# Slave_Mux.net
KiCad netlist of a schematic drawn in EAGLE
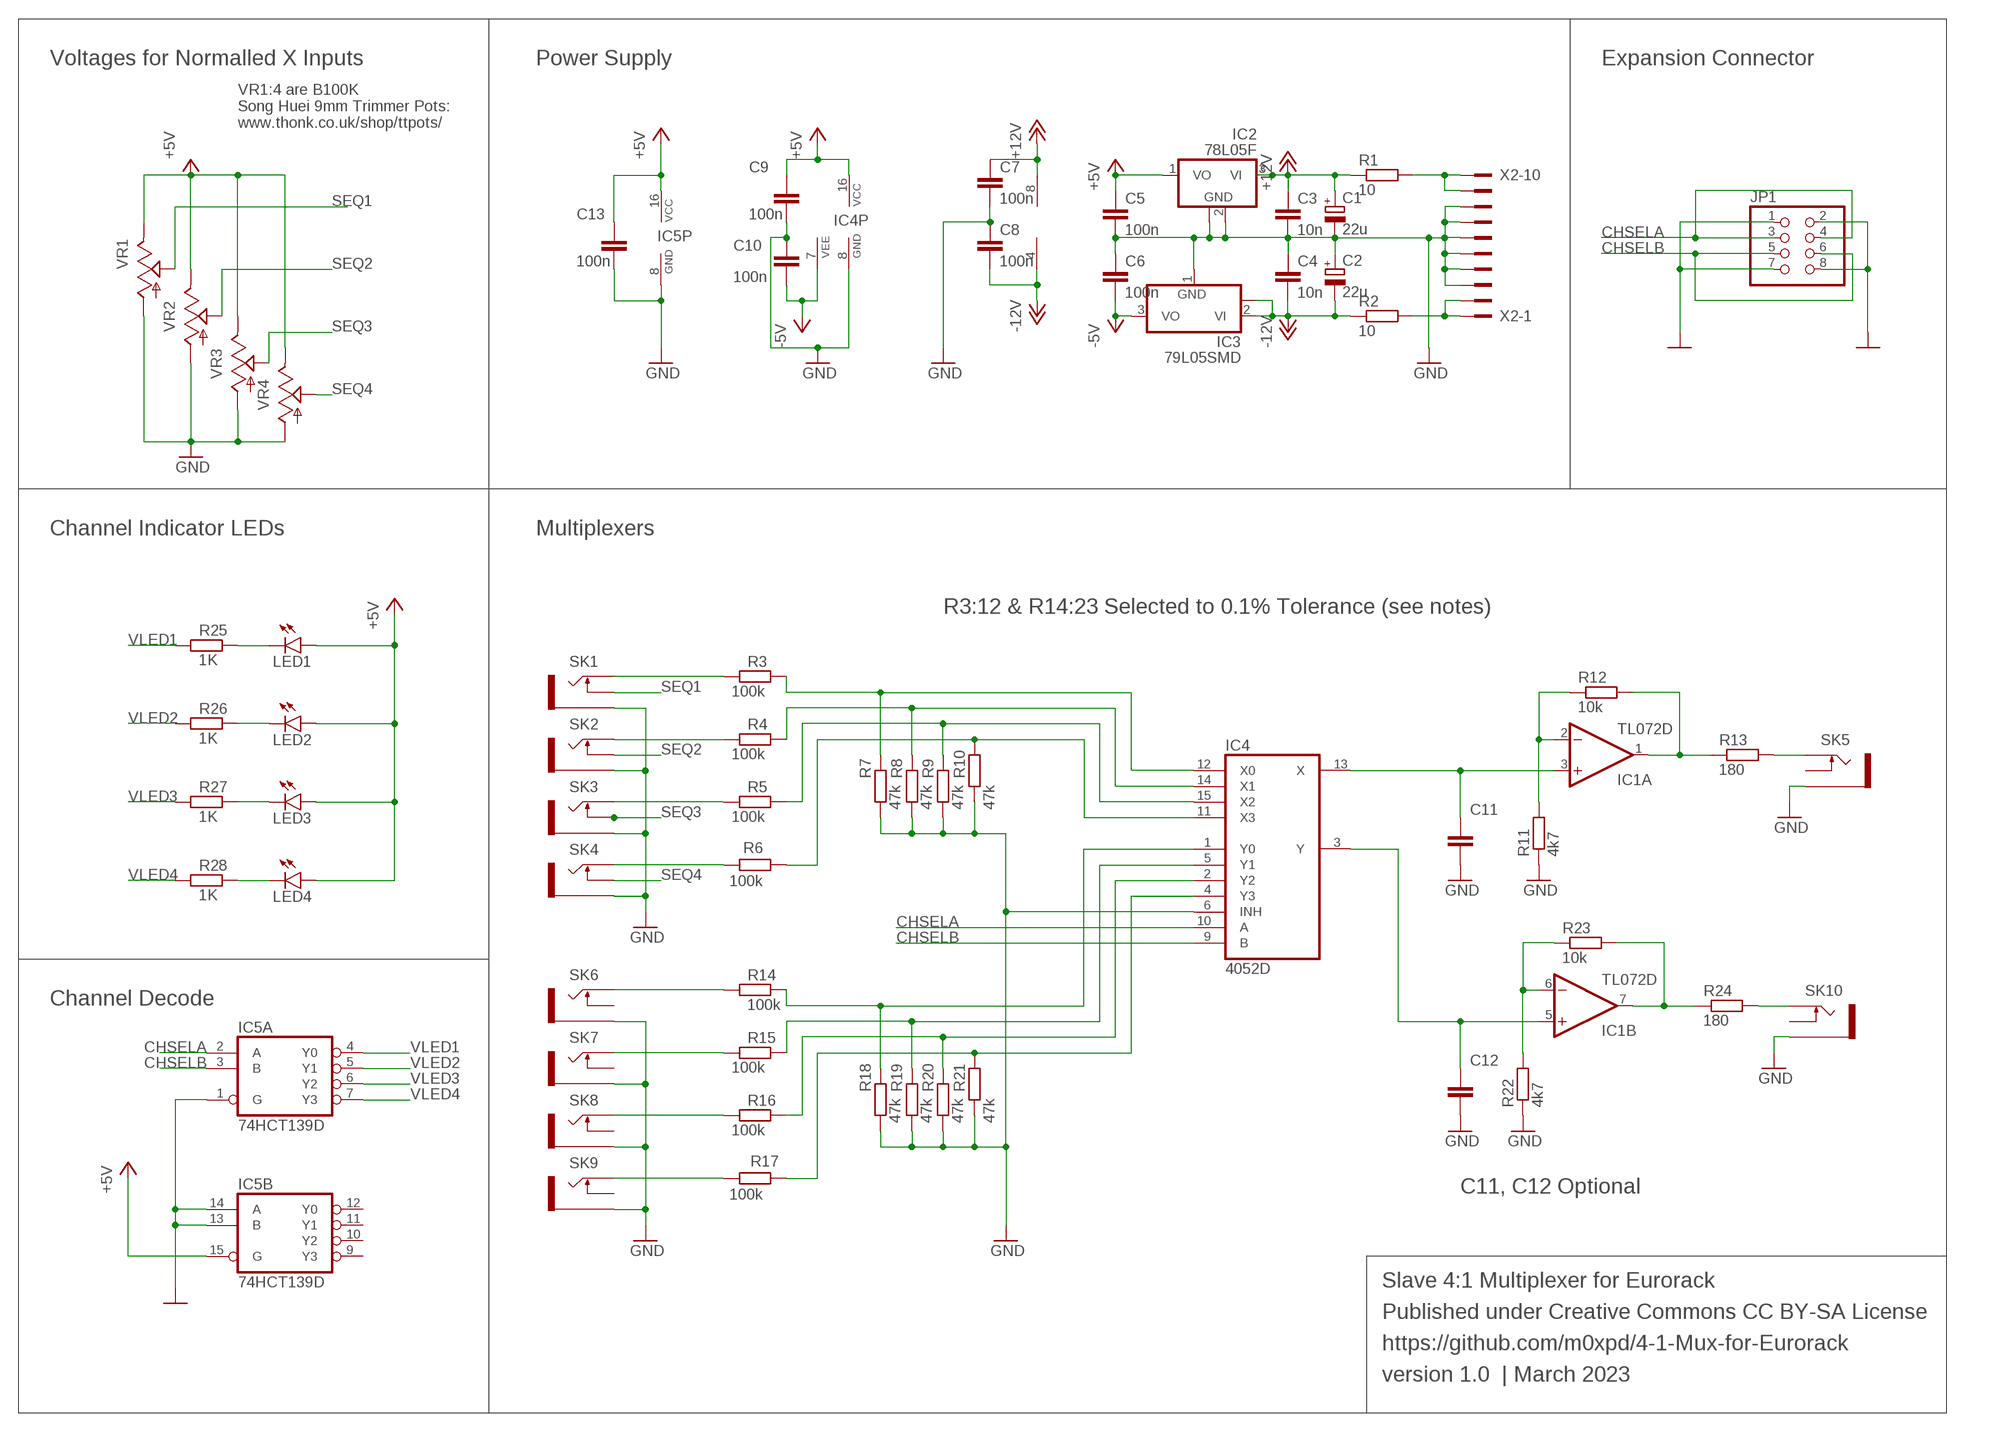
[diagram p0: schematic, sheet 1]

(export (version "E")
  (design (tool "Eeschema 10.0.6"))
  (components
    (comp (ref "C1")
      (value "22u")
      (footprint "eagle-import:153CLV-0505")
      (libsource (lib "eagle-import") (part "CPOL-EU153CLV-0505"))
    )
    (comp (ref "C2")
      (value "22u")
      (footprint "eagle-import:153CLV-0505")
      (libsource (lib "eagle-import") (part "CPOL-EU153CLV-0505"))
    )
    (comp (ref "C3")
      (value "10n")
      (footprint "eagle-import:C1206")
      (libsource (lib "eagle-import") (part "C-EUC1206"))
    )
    (comp (ref "C4")
      (value "10n")
      (footprint "eagle-import:C1206")
      (libsource (lib "eagle-import") (part "C-EUC1206"))
    )
    (comp (ref "C5")
      (value "100n")
      (footprint "eagle-import:C1206")
      (libsource (lib "eagle-import") (part "C-EUC1206"))
    )
    (comp (ref "C6")
      (value "100n")
      (footprint "eagle-import:C1206")
      (libsource (lib "eagle-import") (part "C-EUC1206"))
    )
    (comp (ref "C7")
      (value "100n")
      (footprint "eagle-import:C1206")
      (libsource (lib "eagle-import") (part "C-EUC1206"))
    )
    (comp (ref "C8")
      (value "100n")
      (footprint "eagle-import:C1206")
      (libsource (lib "eagle-import") (part "C-EUC1206"))
    )
    (comp (ref "C9")
      (value "100n")
      (footprint "eagle-import:C1206")
      (libsource (lib "eagle-import") (part "C-EUC1206"))
    )
    (comp (ref "C10")
      (value "100n")
      (footprint "eagle-import:C1206")
      (libsource (lib "eagle-import") (part "C-EUC1206"))
    )
    (comp (ref "C11")
      (value "C-EUC1206")
      (footprint "eagle-import:C1206")
      (libsource (lib "eagle-import") (part "C-EUC1206"))
    )
    (comp (ref "C12")
      (value "C-EUC1206")
      (footprint "eagle-import:C1206")
      (libsource (lib "eagle-import") (part "C-EUC1206"))
    )
    (comp (ref "C13")
      (value "100n")
      (footprint "eagle-import:C1206")
      (libsource (lib "eagle-import") (part "C-EUC1206"))
    )
    (comp (ref "IC1")
      (value "TL072D")
      (footprint "eagle-import:SO08")
      (libsource (lib "eagle-import") (part "TL072D"))
    )
    (comp (ref "IC2")
      (value "78L05F")
      (footprint "eagle-import:SOT89")
      (libsource (lib "eagle-import") (part "78LF05"))
    )
    (comp (ref "IC3")
      (value "79L05SMD")
      (footprint "eagle-import:SOT89")
      (libsource (lib "eagle-import") (part "79L05SMD"))
    )
    (comp (ref "IC4")
      (value "4052D")
      (footprint "eagle-import:SO16")
      (libsource (lib "eagle-import") (part "4052D"))
    )
    (comp (ref "IC5")
      (value "74HCT139D")
      (footprint "eagle-import:SO16")
      (libsource (lib "eagle-import") (part "74139DHCT"))
    )
    (comp (ref "JP1")
      (value "PINHD-2X4")
      (footprint "eagle-import:2X04")
      (libsource (lib "eagle-import") (part "PINHD-2X4"))
    )
    (comp (ref "LED1")
      (value "LED3MM")
      (footprint "eagle-import:LED3MM")
      (libsource (lib "eagle-import") (part "LED3MM"))
    )
    (comp (ref "LED2")
      (value "LED3MM")
      (footprint "eagle-import:LED3MM")
      (libsource (lib "eagle-import") (part "LED3MM"))
    )
    (comp (ref "LED3")
      (value "LED3MM")
      (footprint "eagle-import:LED3MM")
      (libsource (lib "eagle-import") (part "LED3MM"))
    )
    (comp (ref "LED4")
      (value "LED3MM")
      (footprint "eagle-import:LED3MM")
      (libsource (lib "eagle-import") (part "LED3MM"))
    )
    (comp (ref "R1")
      (value "10")
      (footprint "eagle-import:M1206")
      (libsource (lib "eagle-import") (part "R-EU_M1206"))
    )
    (comp (ref "R2")
      (value "10")
      (footprint "eagle-import:M1206")
      (libsource (lib "eagle-import") (part "R-EU_M1206"))
    )
    (comp (ref "R3")
      (value "100k")
      (footprint "eagle-import:M1206")
      (libsource (lib "eagle-import") (part "R-EU_M1206"))
    )
    (comp (ref "R4")
      (value "100k")
      (footprint "eagle-import:M1206")
      (libsource (lib "eagle-import") (part "R-EU_M1206"))
    )
    (comp (ref "R5")
      (value "100k")
      (footprint "eagle-import:M1206")
      (libsource (lib "eagle-import") (part "R-EU_M1206"))
    )
    (comp (ref "R6")
      (value "100k")
      (footprint "eagle-import:M1206")
      (libsource (lib "eagle-import") (part "R-EU_M1206"))
    )
    (comp (ref "R7")
      (value "47k")
      (footprint "eagle-import:M1206")
      (libsource (lib "eagle-import") (part "R-EU_M1206"))
    )
    (comp (ref "R8")
      (value "47k")
      (footprint "eagle-import:M1206")
      (libsource (lib "eagle-import") (part "R-EU_M1206"))
    )
    (comp (ref "R9")
      (value "47k")
      (footprint "eagle-import:M1206")
      (libsource (lib "eagle-import") (part "R-EU_M1206"))
    )
    (comp (ref "R10")
      (value "47k")
      (footprint "eagle-import:M1206")
      (libsource (lib "eagle-import") (part "R-EU_M1206"))
    )
    (comp (ref "R11")
      (value "4k7")
      (footprint "eagle-import:R1206")
      (libsource (lib "eagle-import") (part "R-EU_R1206"))
    )
    (comp (ref "R12")
      (value "10k")
      (footprint "eagle-import:R1206")
      (libsource (lib "eagle-import") (part "R-EU_R1206"))
    )
    (comp (ref "R13")
      (value "180")
      (footprint "eagle-import:M1206")
      (libsource (lib "eagle-import") (part "R-EU_M1206"))
    )
    (comp (ref "R14")
      (value "100k")
      (footprint "eagle-import:M1206")
      (libsource (lib "eagle-import") (part "R-EU_M1206"))
    )
    (comp (ref "R15")
      (value "100k")
      (footprint "eagle-import:M1206")
      (libsource (lib "eagle-import") (part "R-EU_M1206"))
    )
    (comp (ref "R16")
      (value "100k")
      (footprint "eagle-import:M1206")
      (libsource (lib "eagle-import") (part "R-EU_M1206"))
    )
    (comp (ref "R17")
      (value "100k")
      (footprint "eagle-import:M1206")
      (libsource (lib "eagle-import") (part "R-EU_M1206"))
    )
    (comp (ref "R18")
      (value "47k")
      (footprint "eagle-import:M1206")
      (libsource (lib "eagle-import") (part "R-EU_M1206"))
    )
    (comp (ref "R19")
      (value "47k")
      (footprint "eagle-import:M1206")
      (libsource (lib "eagle-import") (part "R-EU_M1206"))
    )
    (comp (ref "R20")
      (value "47k")
      (footprint "eagle-import:M1206")
      (libsource (lib "eagle-import") (part "R-EU_M1206"))
    )
    (comp (ref "R21")
      (value "47k")
      (footprint "eagle-import:M1206")
      (libsource (lib "eagle-import") (part "R-EU_M1206"))
    )
    (comp (ref "R22")
      (value "4k7")
      (footprint "eagle-import:R1206")
      (libsource (lib "eagle-import") (part "R-EU_R1206"))
    )
    (comp (ref "R23")
      (value "10k")
      (footprint "eagle-import:R1206")
      (libsource (lib "eagle-import") (part "R-EU_R1206"))
    )
    (comp (ref "R24")
      (value "180")
      (footprint "eagle-import:M1206")
      (libsource (lib "eagle-import") (part "R-EU_M1206"))
    )
    (comp (ref "R25")
      (value "1K")
      (footprint "eagle-import:M1206")
      (libsource (lib "eagle-import") (part "R-EU_M1206"))
    )
    (comp (ref "R26")
      (value "1K")
      (footprint "eagle-import:M1206")
      (libsource (lib "eagle-import") (part "R-EU_M1206"))
    )
    (comp (ref "R27")
      (value "1K")
      (footprint "eagle-import:M1206")
      (libsource (lib "eagle-import") (part "R-EU_M1206"))
    )
    (comp (ref "R28")
      (value "1K")
      (footprint "eagle-import:M1206")
      (libsource (lib "eagle-import") (part "R-EU_M1206"))
    )
    (comp (ref "SK1")
      (value "THONKICONN_JACK")
      (footprint "eagle-import:WQP-PJ301M-12_JACK")
      (libsource (lib "eagle-import") (part "THONKICONN_JACK"))
    )
    (comp (ref "SK2")
      (value "THONKICONN_JACK")
      (footprint "eagle-import:WQP-PJ301M-12_JACK")
      (libsource (lib "eagle-import") (part "THONKICONN_JACK"))
    )
    (comp (ref "SK3")
      (value "THONKICONN_JACK")
      (footprint "eagle-import:WQP-PJ301M-12_JACK")
      (libsource (lib "eagle-import") (part "THONKICONN_JACK"))
    )
    (comp (ref "SK4")
      (value "THONKICONN_JACK")
      (footprint "eagle-import:WQP-PJ301M-12_JACK")
      (libsource (lib "eagle-import") (part "THONKICONN_JACK"))
    )
    (comp (ref "SK5")
      (value "THONKICONN_JACK")
      (footprint "eagle-import:WQP-PJ301M-12_JACK")
      (libsource (lib "eagle-import") (part "THONKICONN_JACK"))
    )
    (comp (ref "SK6")
      (value "THONKICONN_JACK")
      (footprint "eagle-import:WQP-PJ301M-12_JACK")
      (libsource (lib "eagle-import") (part "THONKICONN_JACK"))
    )
    (comp (ref "SK7")
      (value "THONKICONN_JACK")
      (footprint "eagle-import:WQP-PJ301M-12_JACK")
      (libsource (lib "eagle-import") (part "THONKICONN_JACK"))
    )
    (comp (ref "SK8")
      (value "THONKICONN_JACK")
      (footprint "eagle-import:WQP-PJ301M-12_JACK")
      (libsource (lib "eagle-import") (part "THONKICONN_JACK"))
    )
    (comp (ref "SK9")
      (value "THONKICONN_JACK")
      (footprint "eagle-import:WQP-PJ301M-12_JACK")
      (libsource (lib "eagle-import") (part "THONKICONN_JACK"))
    )
    (comp (ref "SK10")
      (value "THONKICONN_JACK")
      (footprint "eagle-import:WQP-PJ301M-12_JACK")
      (libsource (lib "eagle-import") (part "THONKICONN_JACK"))
    )
    (comp (ref "VR1")
      (value "9MM_VERTICAL_POT")
      (footprint "eagle-import:9MM_SNAP-IN_POT")
      (libsource (lib "eagle-import") (part "9MM_VERTICAL_POT"))
    )
    (comp (ref "VR2")
      (value "9MM_VERTICAL_POT")
      (footprint "eagle-import:9MM_SNAP-IN_POT")
      (libsource (lib "eagle-import") (part "9MM_VERTICAL_POT"))
    )
    (comp (ref "VR3")
      (value "9MM_VERTICAL_POT")
      (footprint "eagle-import:9MM_SNAP-IN_POT")
      (libsource (lib "eagle-import") (part "9MM_VERTICAL_POT"))
    )
    (comp (ref "VR4")
      (value "9MM_VERTICAL_POT")
      (footprint "eagle-import:9MM_SNAP-IN_POT")
      (libsource (lib "eagle-import") (part "9MM_VERTICAL_POT"))
    )
    (comp (ref "X2")
      (value "2510-")
      (footprint "eagle-import:PAK100_2500-10")
      (fields (field (name "MF") "3M") (field (name "MPN") "2510-6002UB"))
      (libsource (lib "eagle-import") (part "2510-"))
    )
  )
  (nets
    (net (code "1") (name "+5V") (class "Default")
      (node (ref "C13") (pin "1") (pinfunction "1_1") (pintype "passive"))
      (node (ref "C5") (pin "1") (pinfunction "1_1") (pintype "passive"))
      (node (ref "C9") (pin "1") (pinfunction "1_1") (pintype "passive"))
      (node (ref "IC2") (pin "1") (pinfunction "VO_1") (pintype "passive"))
      (node (ref "IC4") (pin "16") (pinfunction "VCC_16") (pintype "power_in"))
      (node (ref "IC5") (pin "15") (pinfunction "G_15") (pintype "input"))
      (node (ref "IC5") (pin "16") (pinfunction "VCC_16") (pintype "power_in"))
      (node (ref "LED1") (pin "A") (pinfunction "A_A") (pintype "passive"))
      (node (ref "LED2") (pin "A") (pinfunction "A_A") (pintype "passive"))
      (node (ref "LED3") (pin "A") (pinfunction "A_A") (pintype "passive"))
      (node (ref "LED4") (pin "A") (pinfunction "A_A") (pintype "passive"))
      (node (ref "VR1") (pin "3") (pinfunction "E_3") (pintype "passive"))
      (node (ref "VR2") (pin "3") (pinfunction "E_3") (pintype "passive"))
      (node (ref "VR3") (pin "3") (pinfunction "E_3") (pintype "passive"))
      (node (ref "VR4") (pin "3") (pinfunction "E_3") (pintype "passive"))
    )
    (net (code "2") (name "+12V") (class "Default")
      (node (ref "C1") (pin "+") (pinfunction "+_+") (pintype "passive"))
      (node (ref "C3") (pin "1") (pinfunction "1_1") (pintype "passive"))
      (node (ref "C7") (pin "1") (pinfunction "1_1") (pintype "passive"))
      (node (ref "IC1") (pin "8") (pinfunction "V+_8") (pintype "power_in"))
      (node (ref "IC2") (pin "3") (pinfunction "VI_3") (pintype "input"))
      (node (ref "R1") (pin "1") (pinfunction "1_1") (pintype "passive"))
    )
    (net (code "3") (name "-5V") (class "Default")
      (node (ref "C10") (pin "2") (pinfunction "2_2") (pintype "passive"))
      (node (ref "C6") (pin "2") (pinfunction "2_2") (pintype "passive"))
      (node (ref "IC3") (pin "3") (pinfunction "VO_3") (pintype "passive"))
      (node (ref "IC4") (pin "7") (pinfunction "VEE_7") (pintype "power_in"))
    )
    (net (code "4") (name "-12V") (class "Default")
      (node (ref "C2") (pin "-") (pinfunction "-_-") (pintype "passive"))
      (node (ref "C4") (pin "2") (pinfunction "2_2") (pintype "passive"))
      (node (ref "C8") (pin "2") (pinfunction "2_2") (pintype "passive"))
      (node (ref "IC1") (pin "4") (pinfunction "V-_4") (pintype "power_in"))
      (node (ref "IC3") (pin "2") (pinfunction "VI_2") (pintype "input"))
      (node (ref "IC3") (pin "2@1") (pinfunction "VI_2@1") (pintype "passive"))
      (node (ref "R2") (pin "1") (pinfunction "1_1") (pintype "passive"))
    )
    (net (code "5") (name "/CHSELA") (class "Default")
      (node (ref "IC4") (pin "10") (pinfunction "A_10") (pintype "input"))
      (node (ref "IC5") (pin "2") (pinfunction "A_2") (pintype "input"))
      (node (ref "JP1") (pin "3") (pinfunction "3_3") (pintype "passive"))
      (node (ref "JP1") (pin "4") (pinfunction "4_4") (pintype "passive"))
    )
    (net (code "6") (name "/CHSELB") (class "Default")
      (node (ref "IC4") (pin "9") (pinfunction "B_9") (pintype "input"))
      (node (ref "IC5") (pin "3") (pinfunction "B_3") (pintype "input"))
      (node (ref "JP1") (pin "5") (pinfunction "5_5") (pintype "passive"))
      (node (ref "JP1") (pin "6") (pinfunction "6_6") (pintype "passive"))
    )
    (net (code "7") (name "/SEQ1") (class "Default")
      (node (ref "SK1") (pin "P$2_SWITCH") (pinfunction "SWITCH_P$2_SWITCH") (pintype "passive"))
      (node (ref "VR1") (pin "2") (pinfunction "S_2") (pintype "passive"))
    )
    (net (code "8") (name "/SEQ2") (class "Default")
      (node (ref "SK2") (pin "P$2_SWITCH") (pinfunction "SWITCH_P$2_SWITCH") (pintype "passive"))
      (node (ref "VR2") (pin "2") (pinfunction "S_2") (pintype "passive"))
    )
    (net (code "9") (name "/SEQ3") (class "Default")
      (node (ref "SK3") (pin "P$2_SWITCH") (pinfunction "SWITCH_P$2_SWITCH") (pintype "passive"))
      (node (ref "VR3") (pin "2") (pinfunction "S_2") (pintype "passive"))
    )
    (net (code "10") (name "/SEQ4") (class "Default")
      (node (ref "SK4") (pin "P$2_SWITCH") (pinfunction "SWITCH_P$2_SWITCH") (pintype "passive"))
      (node (ref "VR4") (pin "2") (pinfunction "S_2") (pintype "passive"))
    )
    (net (code "11") (name "/VLED1") (class "Default")
      (node (ref "IC5") (pin "4") (pinfunction "Y0_4") (pintype "output"))
      (node (ref "R25") (pin "1") (pinfunction "1_1") (pintype "passive"))
    )
    (net (code "12") (name "/VLED2") (class "Default")
      (node (ref "IC5") (pin "5") (pinfunction "Y1_5") (pintype "output"))
      (node (ref "R26") (pin "1") (pinfunction "1_1") (pintype "passive"))
    )
    (net (code "13") (name "/VLED3") (class "Default")
      (node (ref "IC5") (pin "6") (pinfunction "Y2_6") (pintype "output"))
      (node (ref "R27") (pin "1") (pinfunction "1_1") (pintype "passive"))
    )
    (net (code "14") (name "/VLED4") (class "Default")
      (node (ref "IC5") (pin "7") (pinfunction "Y3_7") (pintype "output"))
      (node (ref "R28") (pin "1") (pinfunction "1_1") (pintype "passive"))
    )
    (net (code "15") (name "GND") (class "Default")
      (node (ref "C1") (pin "-") (pinfunction "-_-") (pintype "passive"))
      (node (ref "C10") (pin "1") (pinfunction "1_1") (pintype "passive"))
      (node (ref "C11") (pin "2") (pinfunction "2_2") (pintype "passive"))
      (node (ref "C12") (pin "2") (pinfunction "2_2") (pintype "passive"))
      (node (ref "C13") (pin "2") (pinfunction "2_2") (pintype "passive"))
      (node (ref "C2") (pin "+") (pinfunction "+_+") (pintype "passive"))
      (node (ref "C3") (pin "2") (pinfunction "2_2") (pintype "passive"))
      (node (ref "C4") (pin "1") (pinfunction "1_1") (pintype "passive"))
      (node (ref "C5") (pin "2") (pinfunction "2_2") (pintype "passive"))
      (node (ref "C6") (pin "1") (pinfunction "1_1") (pintype "passive"))
      (node (ref "C7") (pin "2") (pinfunction "2_2") (pintype "passive"))
      (node (ref "C8") (pin "1") (pinfunction "1_1") (pintype "passive"))
      (node (ref "C9") (pin "2") (pinfunction "2_2") (pintype "passive"))
      (node (ref "IC2") (pin "2") (pinfunction "GND_2") (pintype "passive"))
      (node (ref "IC2") (pin "2@1") (pinfunction "GND_2@1") (pintype "passive"))
      (node (ref "IC3") (pin "1") (pinfunction "GND_1") (pintype "passive"))
      (node (ref "IC4") (pin "6") (pinfunction "INH_6") (pintype "input"))
      (node (ref "IC4") (pin "8") (pinfunction "GND_8") (pintype "power_in"))
      (node (ref "IC5") (pin "1") (pinfunction "G_1") (pintype "input"))
      (node (ref "IC5") (pin "13") (pinfunction "B_13") (pintype "input"))
      (node (ref "IC5") (pin "14") (pinfunction "A_14") (pintype "input"))
      (node (ref "IC5") (pin "8") (pinfunction "GND_8") (pintype "power_in"))
      (node (ref "JP1") (pin "1") (pinfunction "1_1") (pintype "passive"))
      (node (ref "JP1") (pin "2") (pinfunction "2_2") (pintype "passive"))
      (node (ref "JP1") (pin "7") (pinfunction "7_7") (pintype "passive"))
      (node (ref "JP1") (pin "8") (pinfunction "8_8") (pintype "passive"))
      (node (ref "R10") (pin "1") (pinfunction "1_1") (pintype "passive"))
      (node (ref "R11") (pin "1") (pinfunction "1_1") (pintype "passive"))
      (node (ref "R18") (pin "1") (pinfunction "1_1") (pintype "passive"))
      (node (ref "R19") (pin "1") (pinfunction "1_1") (pintype "passive"))
      (node (ref "R20") (pin "1") (pinfunction "1_1") (pintype "passive"))
      (node (ref "R21") (pin "1") (pinfunction "1_1") (pintype "passive"))
      (node (ref "R22") (pin "1") (pinfunction "1_1") (pintype "passive"))
      (node (ref "R7") (pin "1") (pinfunction "1_1") (pintype "passive"))
      (node (ref "R8") (pin "1") (pinfunction "1_1") (pintype "passive"))
      (node (ref "R9") (pin "1") (pinfunction "1_1") (pintype "passive"))
      (node (ref "SK1") (pin "P$3_SLEEVE") (pinfunction "SLEEVE_P$3_SLEEVE") (pintype "passive"))
      (node (ref "SK10") (pin "P$3_SLEEVE") (pinfunction "SLEEVE_P$3_SLEEVE") (pintype "passive"))
      (node (ref "SK2") (pin "P$3_SLEEVE") (pinfunction "SLEEVE_P$3_SLEEVE") (pintype "passive"))
      (node (ref "SK3") (pin "P$3_SLEEVE") (pinfunction "SLEEVE_P$3_SLEEVE") (pintype "passive"))
      (node (ref "SK4") (pin "P$3_SLEEVE") (pinfunction "SLEEVE_P$3_SLEEVE") (pintype "passive"))
      (node (ref "SK5") (pin "P$3_SLEEVE") (pinfunction "SLEEVE_P$3_SLEEVE") (pintype "passive"))
      (node (ref "SK6") (pin "P$3_SLEEVE") (pinfunction "SLEEVE_P$3_SLEEVE") (pintype "passive"))
      (node (ref "SK7") (pin "P$3_SLEEVE") (pinfunction "SLEEVE_P$3_SLEEVE") (pintype "passive"))
      (node (ref "SK8") (pin "P$3_SLEEVE") (pinfunction "SLEEVE_P$3_SLEEVE") (pintype "passive"))
      (node (ref "SK9") (pin "P$3_SLEEVE") (pinfunction "SLEEVE_P$3_SLEEVE") (pintype "passive"))
      (node (ref "VR1") (pin "1") (pinfunction "A_1") (pintype "passive"))
      (node (ref "VR2") (pin "1") (pinfunction "A_1") (pintype "passive"))
      (node (ref "VR3") (pin "1") (pinfunction "A_1") (pintype "passive"))
      (node (ref "VR4") (pin "1") (pinfunction "A_1") (pintype "passive"))
      (node (ref "X2") (pin "3") (pinfunction "KL_3") (pintype "passive"))
      (node (ref "X2") (pin "4") (pinfunction "KL_4") (pintype "passive"))
      (node (ref "X2") (pin "5") (pinfunction "KL_5") (pintype "passive"))
      (node (ref "X2") (pin "6") (pinfunction "KL_6") (pintype "passive"))
      (node (ref "X2") (pin "7") (pinfunction "KL_7") (pintype "passive"))
      (node (ref "X2") (pin "8") (pinfunction "KL_8") (pintype "passive"))
    )
    (net (code "16") (name "Net-(IC1A-+IN)") (class "Default")
      (node (ref "C11") (pin "1") (pinfunction "1_1") (pintype "passive"))
      (node (ref "IC1") (pin "3") (pinfunction "+IN_3") (pintype "input"))
      (node (ref "IC4") (pin "13") (pinfunction "X_13") (pintype "bidirectional"))
    )
    (net (code "17") (name "Net-(IC1A--IN)") (class "Default")
      (node (ref "IC1") (pin "2") (pinfunction "-IN_2") (pintype "input"))
      (node (ref "R11") (pin "2") (pinfunction "2_2") (pintype "passive"))
      (node (ref "R12") (pin "1") (pinfunction "1_1") (pintype "passive"))
    )
    (net (code "18") (name "Net-(IC1A-OUT)") (class "Default")
      (node (ref "IC1") (pin "1") (pinfunction "OUT_1") (pintype "output"))
      (node (ref "R12") (pin "2") (pinfunction "2_2") (pintype "passive"))
      (node (ref "R13") (pin "1") (pinfunction "1_1") (pintype "passive"))
    )
    (net (code "19") (name "Net-(IC1B-+IN)") (class "Default")
      (node (ref "C12") (pin "1") (pinfunction "1_1") (pintype "passive"))
      (node (ref "IC1") (pin "5") (pinfunction "+IN_5") (pintype "input"))
      (node (ref "IC4") (pin "3") (pinfunction "Y_3") (pintype "bidirectional"))
    )
    (net (code "20") (name "Net-(IC1B--IN)") (class "Default")
      (node (ref "IC1") (pin "6") (pinfunction "-IN_6") (pintype "input"))
      (node (ref "R22") (pin "2") (pinfunction "2_2") (pintype "passive"))
      (node (ref "R23") (pin "1") (pinfunction "1_1") (pintype "passive"))
    )
    (net (code "21") (name "Net-(IC1B-OUT)") (class "Default")
      (node (ref "IC1") (pin "7") (pinfunction "OUT_7") (pintype "output"))
      (node (ref "R23") (pin "2") (pinfunction "2_2") (pintype "passive"))
      (node (ref "R24") (pin "1") (pinfunction "1_1") (pintype "passive"))
    )
    (net (code "22") (name "Net-(IC4A-X0)") (class "Default")
      (node (ref "IC4") (pin "12") (pinfunction "X0_12") (pintype "bidirectional"))
      (node (ref "R3") (pin "2") (pinfunction "2_2") (pintype "passive"))
      (node (ref "R7") (pin "2") (pinfunction "2_2") (pintype "passive"))
    )
    (net (code "23") (name "Net-(IC4A-X1)") (class "Default")
      (node (ref "IC4") (pin "14") (pinfunction "X1_14") (pintype "bidirectional"))
      (node (ref "R4") (pin "2") (pinfunction "2_2") (pintype "passive"))
      (node (ref "R8") (pin "2") (pinfunction "2_2") (pintype "passive"))
    )
    (net (code "24") (name "Net-(IC4A-X2)") (class "Default")
      (node (ref "IC4") (pin "15") (pinfunction "X2_15") (pintype "bidirectional"))
      (node (ref "R5") (pin "2") (pinfunction "2_2") (pintype "passive"))
      (node (ref "R9") (pin "2") (pinfunction "2_2") (pintype "passive"))
    )
    (net (code "25") (name "Net-(IC4A-X3)") (class "Default")
      (node (ref "IC4") (pin "11") (pinfunction "X3_11") (pintype "bidirectional"))
      (node (ref "R10") (pin "2") (pinfunction "2_2") (pintype "passive"))
      (node (ref "R6") (pin "1") (pinfunction "1_1") (pintype "passive"))
    )
    (net (code "26") (name "Net-(IC4A-Y0)") (class "Default")
      (node (ref "IC4") (pin "1") (pinfunction "Y0_1") (pintype "bidirectional"))
      (node (ref "R14") (pin "2") (pinfunction "2_2") (pintype "passive"))
      (node (ref "R18") (pin "2") (pinfunction "2_2") (pintype "passive"))
    )
    (net (code "27") (name "Net-(IC4A-Y1)") (class "Default")
      (node (ref "IC4") (pin "5") (pinfunction "Y1_5") (pintype "bidirectional"))
      (node (ref "R15") (pin "2") (pinfunction "2_2") (pintype "passive"))
      (node (ref "R19") (pin "2") (pinfunction "2_2") (pintype "passive"))
    )
    (net (code "28") (name "Net-(IC4A-Y2)") (class "Default")
      (node (ref "IC4") (pin "2") (pinfunction "Y2_2") (pintype "bidirectional"))
      (node (ref "R16") (pin "2") (pinfunction "2_2") (pintype "passive"))
      (node (ref "R20") (pin "2") (pinfunction "2_2") (pintype "passive"))
    )
    (net (code "29") (name "Net-(IC4A-Y3)") (class "Default")
      (node (ref "IC4") (pin "4") (pinfunction "Y3_4") (pintype "bidirectional"))
      (node (ref "R17") (pin "1") (pinfunction "1_1") (pintype "passive"))
      (node (ref "R21") (pin "2") (pinfunction "2_2") (pintype "passive"))
    )
    (net (code "30") (name "Net-(LED1-C)") (class "Default")
      (node (ref "LED1") (pin "K") (pinfunction "C_K") (pintype "passive"))
      (node (ref "R25") (pin "2") (pinfunction "2_2") (pintype "passive"))
    )
    (net (code "31") (name "Net-(LED2-C)") (class "Default")
      (node (ref "LED2") (pin "K") (pinfunction "C_K") (pintype "passive"))
      (node (ref "R26") (pin "2") (pinfunction "2_2") (pintype "passive"))
    )
    (net (code "32") (name "Net-(LED3-C)") (class "Default")
      (node (ref "LED3") (pin "K") (pinfunction "C_K") (pintype "passive"))
      (node (ref "R27") (pin "2") (pinfunction "2_2") (pintype "passive"))
    )
    (net (code "33") (name "Net-(LED4-C)") (class "Default")
      (node (ref "LED4") (pin "K") (pinfunction "C_K") (pintype "passive"))
      (node (ref "R28") (pin "2") (pinfunction "2_2") (pintype "passive"))
    )
    (net (code "34") (name "Net-(SK1-TIP)") (class "Default")
      (node (ref "R3") (pin "1") (pinfunction "1_1") (pintype "passive"))
      (node (ref "SK1") (pin "P$1_TIP") (pinfunction "TIP_P$1_TIP") (pintype "passive"))
    )
    (net (code "35") (name "Net-(SK2-TIP)") (class "Default")
      (node (ref "R4") (pin "1") (pinfunction "1_1") (pintype "passive"))
      (node (ref "SK2") (pin "P$1_TIP") (pinfunction "TIP_P$1_TIP") (pintype "passive"))
    )
    (net (code "36") (name "Net-(SK3-TIP)") (class "Default")
      (node (ref "R5") (pin "1") (pinfunction "1_1") (pintype "passive"))
      (node (ref "SK3") (pin "P$1_TIP") (pinfunction "TIP_P$1_TIP") (pintype "passive"))
    )
    (net (code "37") (name "Net-(SK4-TIP)") (class "Default")
      (node (ref "R6") (pin "2") (pinfunction "2_2") (pintype "passive"))
      (node (ref "SK4") (pin "P$1_TIP") (pinfunction "TIP_P$1_TIP") (pintype "passive"))
    )
    (net (code "38") (name "Net-(SK5-TIP)") (class "Default")
      (node (ref "R13") (pin "2") (pinfunction "2_2") (pintype "passive"))
      (node (ref "SK5") (pin "P$1_TIP") (pinfunction "TIP_P$1_TIP") (pintype "passive"))
    )
    (net (code "39") (name "Net-(SK6-TIP)") (class "Default")
      (node (ref "R14") (pin "1") (pinfunction "1_1") (pintype "passive"))
      (node (ref "SK6") (pin "P$1_TIP") (pinfunction "TIP_P$1_TIP") (pintype "passive"))
    )
    (net (code "40") (name "Net-(SK7-TIP)") (class "Default")
      (node (ref "R15") (pin "1") (pinfunction "1_1") (pintype "passive"))
      (node (ref "SK7") (pin "P$1_TIP") (pinfunction "TIP_P$1_TIP") (pintype "passive"))
    )
    (net (code "41") (name "Net-(SK8-TIP)") (class "Default")
      (node (ref "R16") (pin "1") (pinfunction "1_1") (pintype "passive"))
      (node (ref "SK8") (pin "P$1_TIP") (pinfunction "TIP_P$1_TIP") (pintype "passive"))
    )
    (net (code "42") (name "Net-(SK9-TIP)") (class "Default")
      (node (ref "R17") (pin "2") (pinfunction "2_2") (pintype "passive"))
      (node (ref "SK9") (pin "P$1_TIP") (pinfunction "TIP_P$1_TIP") (pintype "passive"))
    )
    (net (code "43") (name "Net-(SK10-TIP)") (class "Default")
      (node (ref "R24") (pin "2") (pinfunction "2_2") (pintype "passive"))
      (node (ref "SK10") (pin "P$1_TIP") (pinfunction "TIP_P$1_TIP") (pintype "passive"))
    )
    (net (code "44") (name "Net-(X2A-KL)") (class "Default")
      (node (ref "R2") (pin "2") (pinfunction "2_2") (pintype "passive"))
      (node (ref "X2") (pin "1") (pinfunction "KL_1") (pintype "passive"))
      (node (ref "X2") (pin "2") (pinfunction "KL_2") (pintype "passive"))
    )
    (net (code "45") (name "Net-(X2B-KL)") (class "Default")
      (node (ref "R1") (pin "2") (pinfunction "2_2") (pintype "passive"))
      (node (ref "X2") (pin "10") (pinfunction "KL_10") (pintype "passive"))
      (node (ref "X2") (pin "9") (pinfunction "KL_9") (pintype "passive"))
    )
    (net (code "46") (name "unconnected-(IC5B-Y0-Pad12)") (class "Default")
      (node (ref "IC5") (pin "12") (pinfunction "Y0_12") (pintype "output"))
    )
    (net (code "47") (name "unconnected-(IC5B-Y1-Pad11)") (class "Default")
      (node (ref "IC5") (pin "11") (pinfunction "Y1_11") (pintype "output"))
    )
    (net (code "48") (name "unconnected-(IC5B-Y2-Pad10)") (class "Default")
      (node (ref "IC5") (pin "10") (pinfunction "Y2_10") (pintype "output"))
    )
    (net (code "49") (name "unconnected-(IC5B-Y3-Pad9)") (class "Default")
      (node (ref "IC5") (pin "9") (pinfunction "Y3_9") (pintype "output"))
    )
    (net (code "50") (name "unconnected-(SK5-SWITCH-PadP$2_SWITCH)") (class "Default")
      (node (ref "SK5") (pin "P$2_SWITCH") (pinfunction "SWITCH_P$2_SWITCH") (pintype "passive"))
    )
    (net (code "51") (name "unconnected-(SK6-SWITCH-PadP$2_SWITCH)") (class "Default")
      (node (ref "SK6") (pin "P$2_SWITCH") (pinfunction "SWITCH_P$2_SWITCH") (pintype "passive"))
    )
    (net (code "52") (name "unconnected-(SK7-SWITCH-PadP$2_SWITCH)") (class "Default")
      (node (ref "SK7") (pin "P$2_SWITCH") (pinfunction "SWITCH_P$2_SWITCH") (pintype "passive"))
    )
    (net (code "53") (name "unconnected-(SK8-SWITCH-PadP$2_SWITCH)") (class "Default")
      (node (ref "SK8") (pin "P$2_SWITCH") (pinfunction "SWITCH_P$2_SWITCH") (pintype "passive"))
    )
    (net (code "54") (name "unconnected-(SK9-SWITCH-PadP$2_SWITCH)") (class "Default")
      (node (ref "SK9") (pin "P$2_SWITCH") (pinfunction "SWITCH_P$2_SWITCH") (pintype "passive"))
    )
    (net (code "55") (name "unconnected-(SK10-SWITCH-PadP$2_SWITCH)") (class "Default")
      (node (ref "SK10") (pin "P$2_SWITCH") (pinfunction "SWITCH_P$2_SWITCH") (pintype "passive"))
    )
  )
)
